# circuit.net
KiCad netlist of a schematic drawn in EAGLE
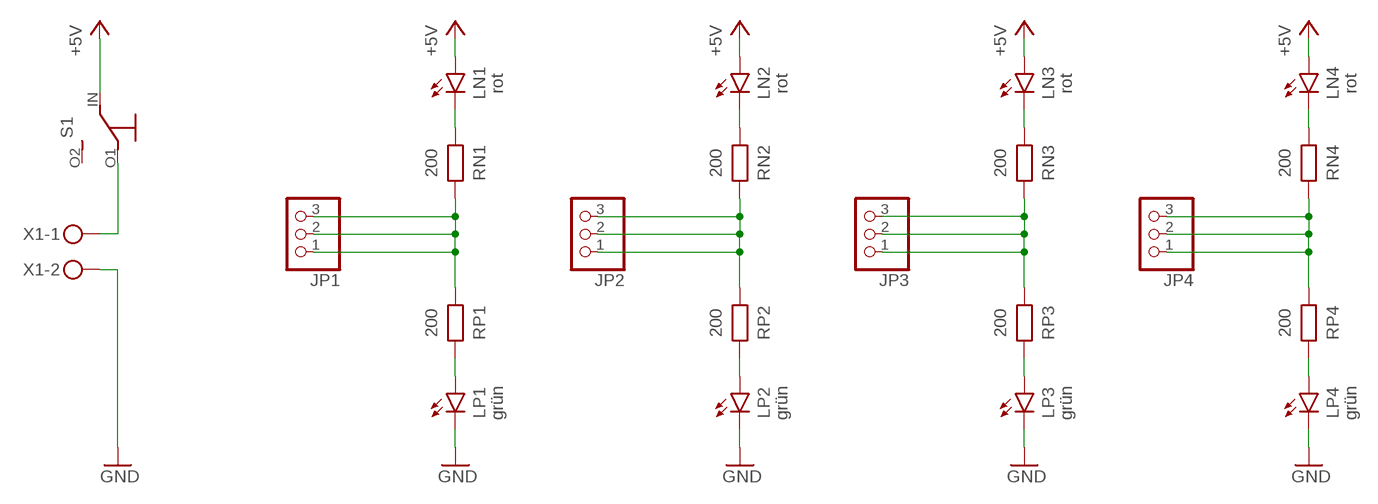
[diagram p0: schematic, sheet 1]

(export (version "E")
  (design (tool "Eeschema 10.0.6"))
  (components
    (comp (ref "JP1")
      (value "PINHD-1X3")
      (footprint "eagle-import:1X03")
      (libsource (lib "eagle-import") (part "PINHD-1X3"))
    )
    (comp (ref "JP2")
      (value "PINHD-1X3")
      (footprint "eagle-import:1X03")
      (libsource (lib "eagle-import") (part "PINHD-1X3"))
    )
    (comp (ref "JP3")
      (value "PINHD-1X3")
      (footprint "eagle-import:1X03")
      (libsource (lib "eagle-import") (part "PINHD-1X3"))
    )
    (comp (ref "JP4")
      (value "PINHD-1X3")
      (footprint "eagle-import:1X03")
      (libsource (lib "eagle-import") (part "PINHD-1X3"))
    )
    (comp (ref "LN1")
      (value "rot")
      (footprint "eagle-import:LED_3MM")
      (libsource (lib "eagle-import") (part "LED-3MM"))
    )
    (comp (ref "LN2")
      (value "rot")
      (footprint "eagle-import:LED_3MM")
      (libsource (lib "eagle-import") (part "LED-3MM"))
    )
    (comp (ref "LN3")
      (value "rot")
      (footprint "eagle-import:LED_3MM")
      (libsource (lib "eagle-import") (part "LED-3MM"))
    )
    (comp (ref "LN4")
      (value "rot")
      (footprint "eagle-import:LED_3MM")
      (libsource (lib "eagle-import") (part "LED-3MM"))
    )
    (comp (ref "LP1")
      (value "grün")
      (footprint "eagle-import:LED_3MM")
      (libsource (lib "eagle-import") (part "LED-3MM"))
    )
    (comp (ref "LP2")
      (value "grün")
      (footprint "eagle-import:LED_3MM")
      (libsource (lib "eagle-import") (part "LED-3MM"))
    )
    (comp (ref "LP3")
      (value "grün")
      (footprint "eagle-import:LED_3MM")
      (libsource (lib "eagle-import") (part "LED-3MM"))
    )
    (comp (ref "LP4")
      (value "grün")
      (footprint "eagle-import:LED_3MM")
      (libsource (lib "eagle-import") (part "LED-3MM"))
    )
    (comp (ref "RN1")
      (value "200")
      (footprint "eagle-import:R_THT_4")
      (libsource (lib "eagle-import") (part "RESISTOR-10MM"))
    )
    (comp (ref "RN2")
      (value "200")
      (footprint "eagle-import:R_THT_4")
      (libsource (lib "eagle-import") (part "RESISTOR-10MM"))
    )
    (comp (ref "RN3")
      (value "200")
      (footprint "eagle-import:R_THT_4")
      (libsource (lib "eagle-import") (part "RESISTOR-10MM"))
    )
    (comp (ref "RN4")
      (value "200")
      (footprint "eagle-import:R_THT_4")
      (libsource (lib "eagle-import") (part "RESISTOR-10MM"))
    )
    (comp (ref "RP1")
      (value "200")
      (footprint "eagle-import:R_THT_4")
      (libsource (lib "eagle-import") (part "RESISTOR-10MM"))
    )
    (comp (ref "RP2")
      (value "200")
      (footprint "eagle-import:R_THT_4")
      (libsource (lib "eagle-import") (part "RESISTOR-10MM"))
    )
    (comp (ref "RP3")
      (value "200")
      (footprint "eagle-import:R_THT_4")
      (libsource (lib "eagle-import") (part "RESISTOR-10MM"))
    )
    (comp (ref "RP4")
      (value "200")
      (footprint "eagle-import:R_THT_4")
      (libsource (lib "eagle-import") (part "RESISTOR-10MM"))
    )
    (comp (ref "S1")
      (value "SCHALTER_UM-KIPP")
      (footprint "eagle-import:SCHALTER_KIPP_UM")
      (libsource (lib "eagle-import") (part "SCHALTER_UM-KIPP"))
    )
    (comp (ref "X1")
      (value "STECKER_SPG_2")
      (footprint "eagle-import:STECKER_SPG_2")
      (libsource (lib "eagle-import") (part "STECKER_SPG_2"))
    )
  )
  (nets
    (net (code "1") (name "+5V") (class "Default")
      (node (ref "LN1") (pin "A") (pinfunction "A_A") (pintype "passive"))
      (node (ref "LN2") (pin "A") (pinfunction "A_A") (pintype "passive"))
      (node (ref "LN3") (pin "A") (pinfunction "A_A") (pintype "passive"))
      (node (ref "LN4") (pin "A") (pinfunction "A_A") (pintype "passive"))
      (node (ref "S1") (pin "IN") (pinfunction "IN_IN") (pintype "passive"))
    )
    (net (code "2") (name "GND") (class "Default")
      (node (ref "LP1") (pin "K") (pinfunction "C_K") (pintype "passive"))
      (node (ref "LP2") (pin "K") (pinfunction "C_K") (pintype "passive"))
      (node (ref "LP3") (pin "K") (pinfunction "C_K") (pintype "passive"))
      (node (ref "LP4") (pin "K") (pinfunction "C_K") (pintype "passive"))
      (node (ref "X1") (pin "2") (pinfunction "KL_2") (pintype "passive"))
    )
    (net (code "3") (name "Net-(LN1-C)") (class "Default")
      (node (ref "LN1") (pin "K") (pinfunction "C_K") (pintype "passive"))
      (node (ref "RN1") (pin "2") (pinfunction "P2_2") (pintype "passive"))
    )
    (net (code "4") (name "Net-(LN2-C)") (class "Default")
      (node (ref "LN2") (pin "K") (pinfunction "C_K") (pintype "passive"))
      (node (ref "RN2") (pin "2") (pinfunction "P2_2") (pintype "passive"))
    )
    (net (code "5") (name "Net-(LN3-C)") (class "Default")
      (node (ref "LN3") (pin "K") (pinfunction "C_K") (pintype "passive"))
      (node (ref "RN3") (pin "2") (pinfunction "P2_2") (pintype "passive"))
    )
    (net (code "6") (name "Net-(LN4-C)") (class "Default")
      (node (ref "LN4") (pin "K") (pinfunction "C_K") (pintype "passive"))
      (node (ref "RN4") (pin "2") (pinfunction "P2_2") (pintype "passive"))
    )
    (net (code "7") (name "Net-(RN1-P1)") (class "Default")
      (node (ref "JP1") (pin "1") (pinfunction "1_1") (pintype "passive"))
      (node (ref "JP1") (pin "2") (pinfunction "2_2") (pintype "passive"))
      (node (ref "JP1") (pin "3") (pinfunction "3_3") (pintype "passive"))
      (node (ref "RN1") (pin "1") (pinfunction "P1_1") (pintype "passive"))
      (node (ref "RP1") (pin "2") (pinfunction "P2_2") (pintype "passive"))
    )
    (net (code "8") (name "Net-(RN2-P1)") (class "Default")
      (node (ref "JP2") (pin "1") (pinfunction "1_1") (pintype "passive"))
      (node (ref "JP2") (pin "2") (pinfunction "2_2") (pintype "passive"))
      (node (ref "JP2") (pin "3") (pinfunction "3_3") (pintype "passive"))
      (node (ref "RN2") (pin "1") (pinfunction "P1_1") (pintype "passive"))
      (node (ref "RP2") (pin "2") (pinfunction "P2_2") (pintype "passive"))
    )
    (net (code "9") (name "Net-(RN3-P1)") (class "Default")
      (node (ref "JP3") (pin "1") (pinfunction "1_1") (pintype "passive"))
      (node (ref "JP3") (pin "2") (pinfunction "2_2") (pintype "passive"))
      (node (ref "JP3") (pin "3") (pinfunction "3_3") (pintype "passive"))
      (node (ref "RN3") (pin "1") (pinfunction "P1_1") (pintype "passive"))
      (node (ref "RP3") (pin "2") (pinfunction "P2_2") (pintype "passive"))
    )
    (net (code "10") (name "Net-(RN4-P1)") (class "Default")
      (node (ref "JP4") (pin "1") (pinfunction "1_1") (pintype "passive"))
      (node (ref "JP4") (pin "2") (pinfunction "2_2") (pintype "passive"))
      (node (ref "JP4") (pin "3") (pinfunction "3_3") (pintype "passive"))
      (node (ref "RN4") (pin "1") (pinfunction "P1_1") (pintype "passive"))
      (node (ref "RP4") (pin "2") (pinfunction "P2_2") (pintype "passive"))
    )
    (net (code "11") (name "Net-(RP1-P1)") (class "Default")
      (node (ref "LP1") (pin "A") (pinfunction "A_A") (pintype "passive"))
      (node (ref "RP1") (pin "1") (pinfunction "P1_1") (pintype "passive"))
    )
    (net (code "12") (name "Net-(RP2-P1)") (class "Default")
      (node (ref "LP2") (pin "A") (pinfunction "A_A") (pintype "passive"))
      (node (ref "RP2") (pin "1") (pinfunction "P1_1") (pintype "passive"))
    )
    (net (code "13") (name "Net-(RP3-P1)") (class "Default")
      (node (ref "LP3") (pin "A") (pinfunction "A_A") (pintype "passive"))
      (node (ref "RP3") (pin "1") (pinfunction "P1_1") (pintype "passive"))
    )
    (net (code "14") (name "Net-(RP4-P1)") (class "Default")
      (node (ref "LP4") (pin "A") (pinfunction "A_A") (pintype "passive"))
      (node (ref "RP4") (pin "1") (pinfunction "P1_1") (pintype "passive"))
    )
    (net (code "15") (name "Net-(X1A-KL)") (class "Default")
      (node (ref "S1") (pin "O1") (pinfunction "O1_O1") (pintype "passive"))
      (node (ref "X1") (pin "1") (pinfunction "KL_1") (pintype "passive"))
    )
    (net (code "16") (name "unconnected-(S1-PadO2)") (class "Default")
      (node (ref "S1") (pin "O2") (pinfunction "O2_O2") (pintype "passive"))
    )
  )
)
